# 1-Tamrin_Aval.net
KiCad netlist of a schematic drawn in Altium Designer
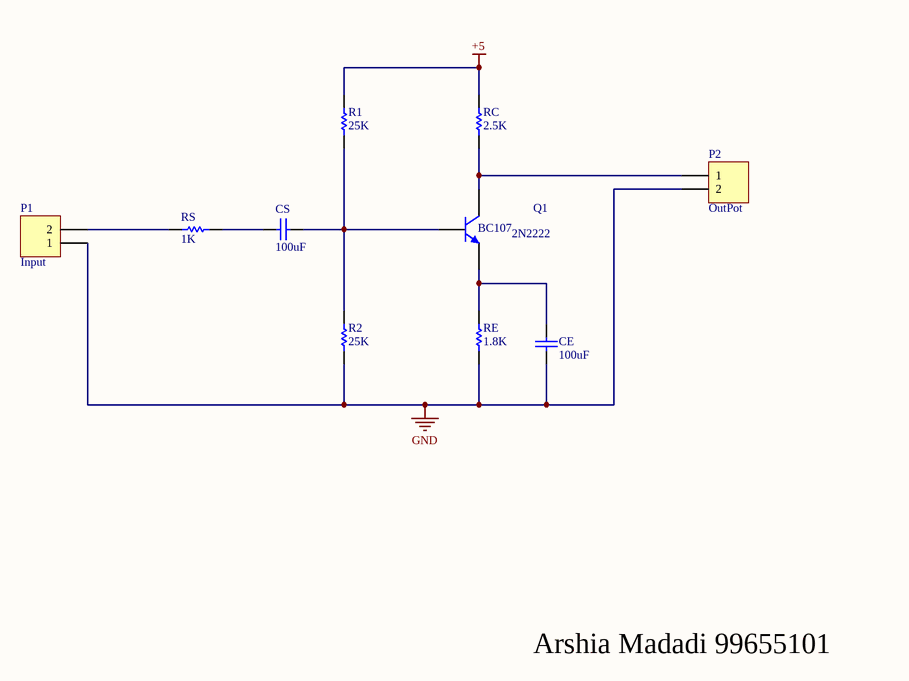
[diagram p0: 1-Tamrin Aval.SchDoc]

(export (version "E")
  (design (tool "Eeschema 10.0.6"))
  (components
    (comp (ref "CE")
      (value "100uF")
      (footprint "CAPC4817X12N")
      (description "CAP 1206")
      (fields (field (name "DESIGNER") "Abbas Basereh"))
      (libsource (lib "Altium") (part "CAP SMD 1206"))
    )
    (comp (ref "CS")
      (value "100uF")
      (footprint "CAPC4817X12N")
      (description "CAP 1206")
      (fields (field (name "DESIGNER") "Abbas Basereh"))
      (libsource (lib "Altium") (part "CAP SMD 1206"))
    )
    (comp (ref "P1")
      (value "Input")
      (footprint "HDR1X2")
      (description "Header, 2-Pin")
      (fields (field (name "PUBLISHER") "Altium Limited"))
      (libsource (lib "") (part "Header 2_1"))
    )
    (comp (ref "P2")
      (value "OutPot")
      (footprint "HDR1X2")
      (description "Header, 2-Pin")
      (fields (field (name "PUBLISHER") "Altium Limited"))
      (libsource (lib "Altium") (part "Header 2"))
    )
    (comp (ref "Q1")
      (value "2N2222")
      (footprint "2N2222")
      (description "NPN Transistor")
      (libsource (lib "Altium") (part "2N2222"))
    )
    (comp (ref "R1")
      (value "25K")
      (footprint "RESC4817X04N")
      (description "RES 1206")
      (fields (field (name "DESIGNER") "Abbas Basereh"))
      (libsource (lib "Altium") (part "RES 1206 0.25W"))
    )
    (comp (ref "R2")
      (value "25K")
      (footprint "RESC4817X04N")
      (description "RES 1206")
      (fields (field (name "DESIGNER") "Abbas Basereh"))
      (libsource (lib "Altium") (part "RES 1206 0.25W"))
    )
    (comp (ref "RC")
      (value "2.5K")
      (footprint "RESC4817X04N")
      (description "RES 1206")
      (fields (field (name "DESIGNER") "Abbas Basereh"))
      (libsource (lib "Altium") (part "RES 1206 0.25W"))
    )
    (comp (ref "RE")
      (value "1.8K")
      (footprint "RESC4817X04N")
      (description "RES 1206")
      (fields (field (name "DESIGNER") "Abbas Basereh"))
      (libsource (lib "Altium") (part "RES 1206 0.25W"))
    )
    (comp (ref "RS")
      (value "1K")
      (footprint "RESC4817X04N")
      (description "RES 1206")
      (fields (field (name "DESIGNER") "Abbas Basereh"))
      (libsource (lib "Altium") (part "RES 1206 0.25W"))
    )
  )
  (nets
    (net (code "1") (name "+5") (class "Default")
      (node (ref "R1") (pin "2") (pinfunction "2_2") (pintype "passive"))
      (node (ref "RC") (pin "2") (pinfunction "2_2") (pintype "passive"))
    )
    (net (code "2") (name "GND") (class "Default")
      (node (ref "CE") (pin "1") (pinfunction "1_1") (pintype "passive"))
      (node (ref "P1") (pin "1") (pinfunction "1_1") (pintype "passive"))
      (node (ref "P2") (pin "2") (pinfunction "2_2") (pintype "passive"))
      (node (ref "R2") (pin "1") (pinfunction "1_1") (pintype "passive"))
      (node (ref "RE") (pin "1") (pinfunction "1_1") (pintype "passive"))
    )
    (net (code "3") (name "Net-(CS-Pad2)") (class "Default")
      (node (ref "CS") (pin "2") (pinfunction "2_2") (pintype "passive"))
      (node (ref "RS") (pin "1") (pinfunction "1_1") (pintype "passive"))
    )
    (net (code "4") (name "Net-(P1-Pad2)") (class "Default")
      (node (ref "P1") (pin "2") (pinfunction "2_2") (pintype "passive"))
      (node (ref "RS") (pin "2") (pinfunction "2_2") (pintype "passive"))
    )
    (net (code "5") (name "Net-(Q1-B)") (class "Default")
      (node (ref "CS") (pin "1") (pinfunction "1_1") (pintype "passive"))
      (node (ref "Q1") (pin "2") (pinfunction "B_2") (pintype "passive"))
      (node (ref "R1") (pin "1") (pinfunction "1_1") (pintype "passive"))
      (node (ref "R2") (pin "2") (pinfunction "2_2") (pintype "passive"))
    )
    (net (code "6") (name "Net-(Q1-C)") (class "Default")
      (node (ref "P2") (pin "1") (pinfunction "1_1") (pintype "passive"))
      (node (ref "Q1") (pin "3") (pinfunction "C_3") (pintype "passive"))
      (node (ref "RC") (pin "1") (pinfunction "1_1") (pintype "passive"))
    )
    (net (code "7") (name "Net-(Q1-E)") (class "Default")
      (node (ref "CE") (pin "2") (pinfunction "2_2") (pintype "passive"))
      (node (ref "Q1") (pin "1") (pinfunction "E_1") (pintype "passive"))
      (node (ref "RE") (pin "2") (pinfunction "2_2") (pintype "passive"))
    )
  )
)
